# DAC_Shield_Rev_B.net
KiCad netlist of a schematic drawn in EAGLE
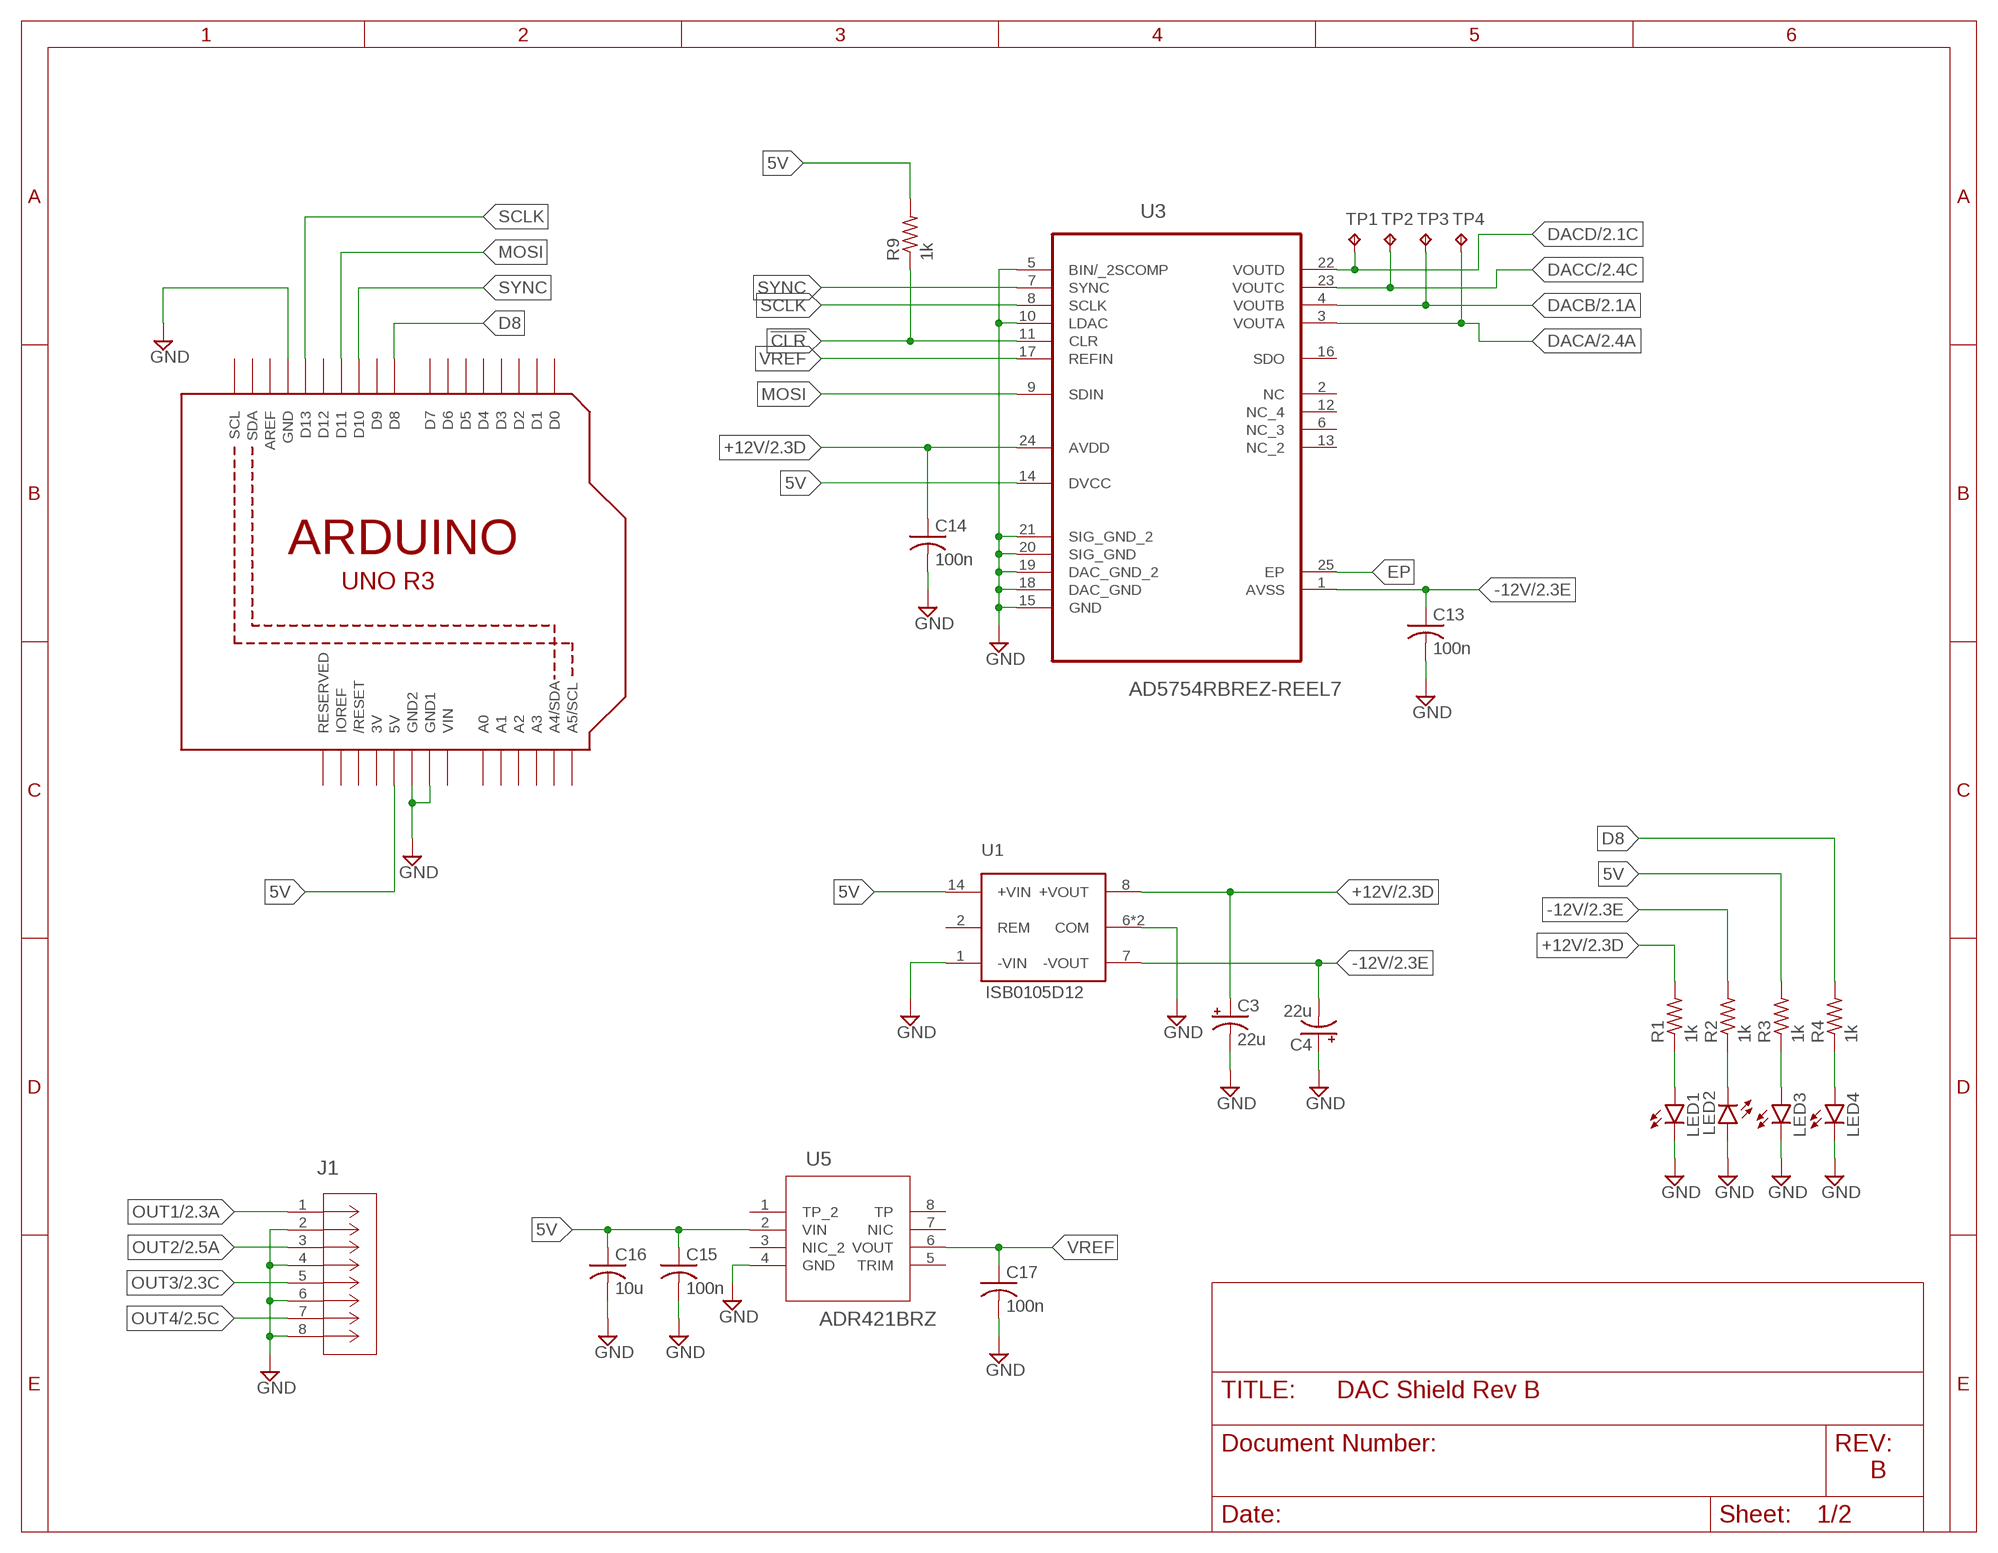
[diagram p0: schematic, sheet 1]
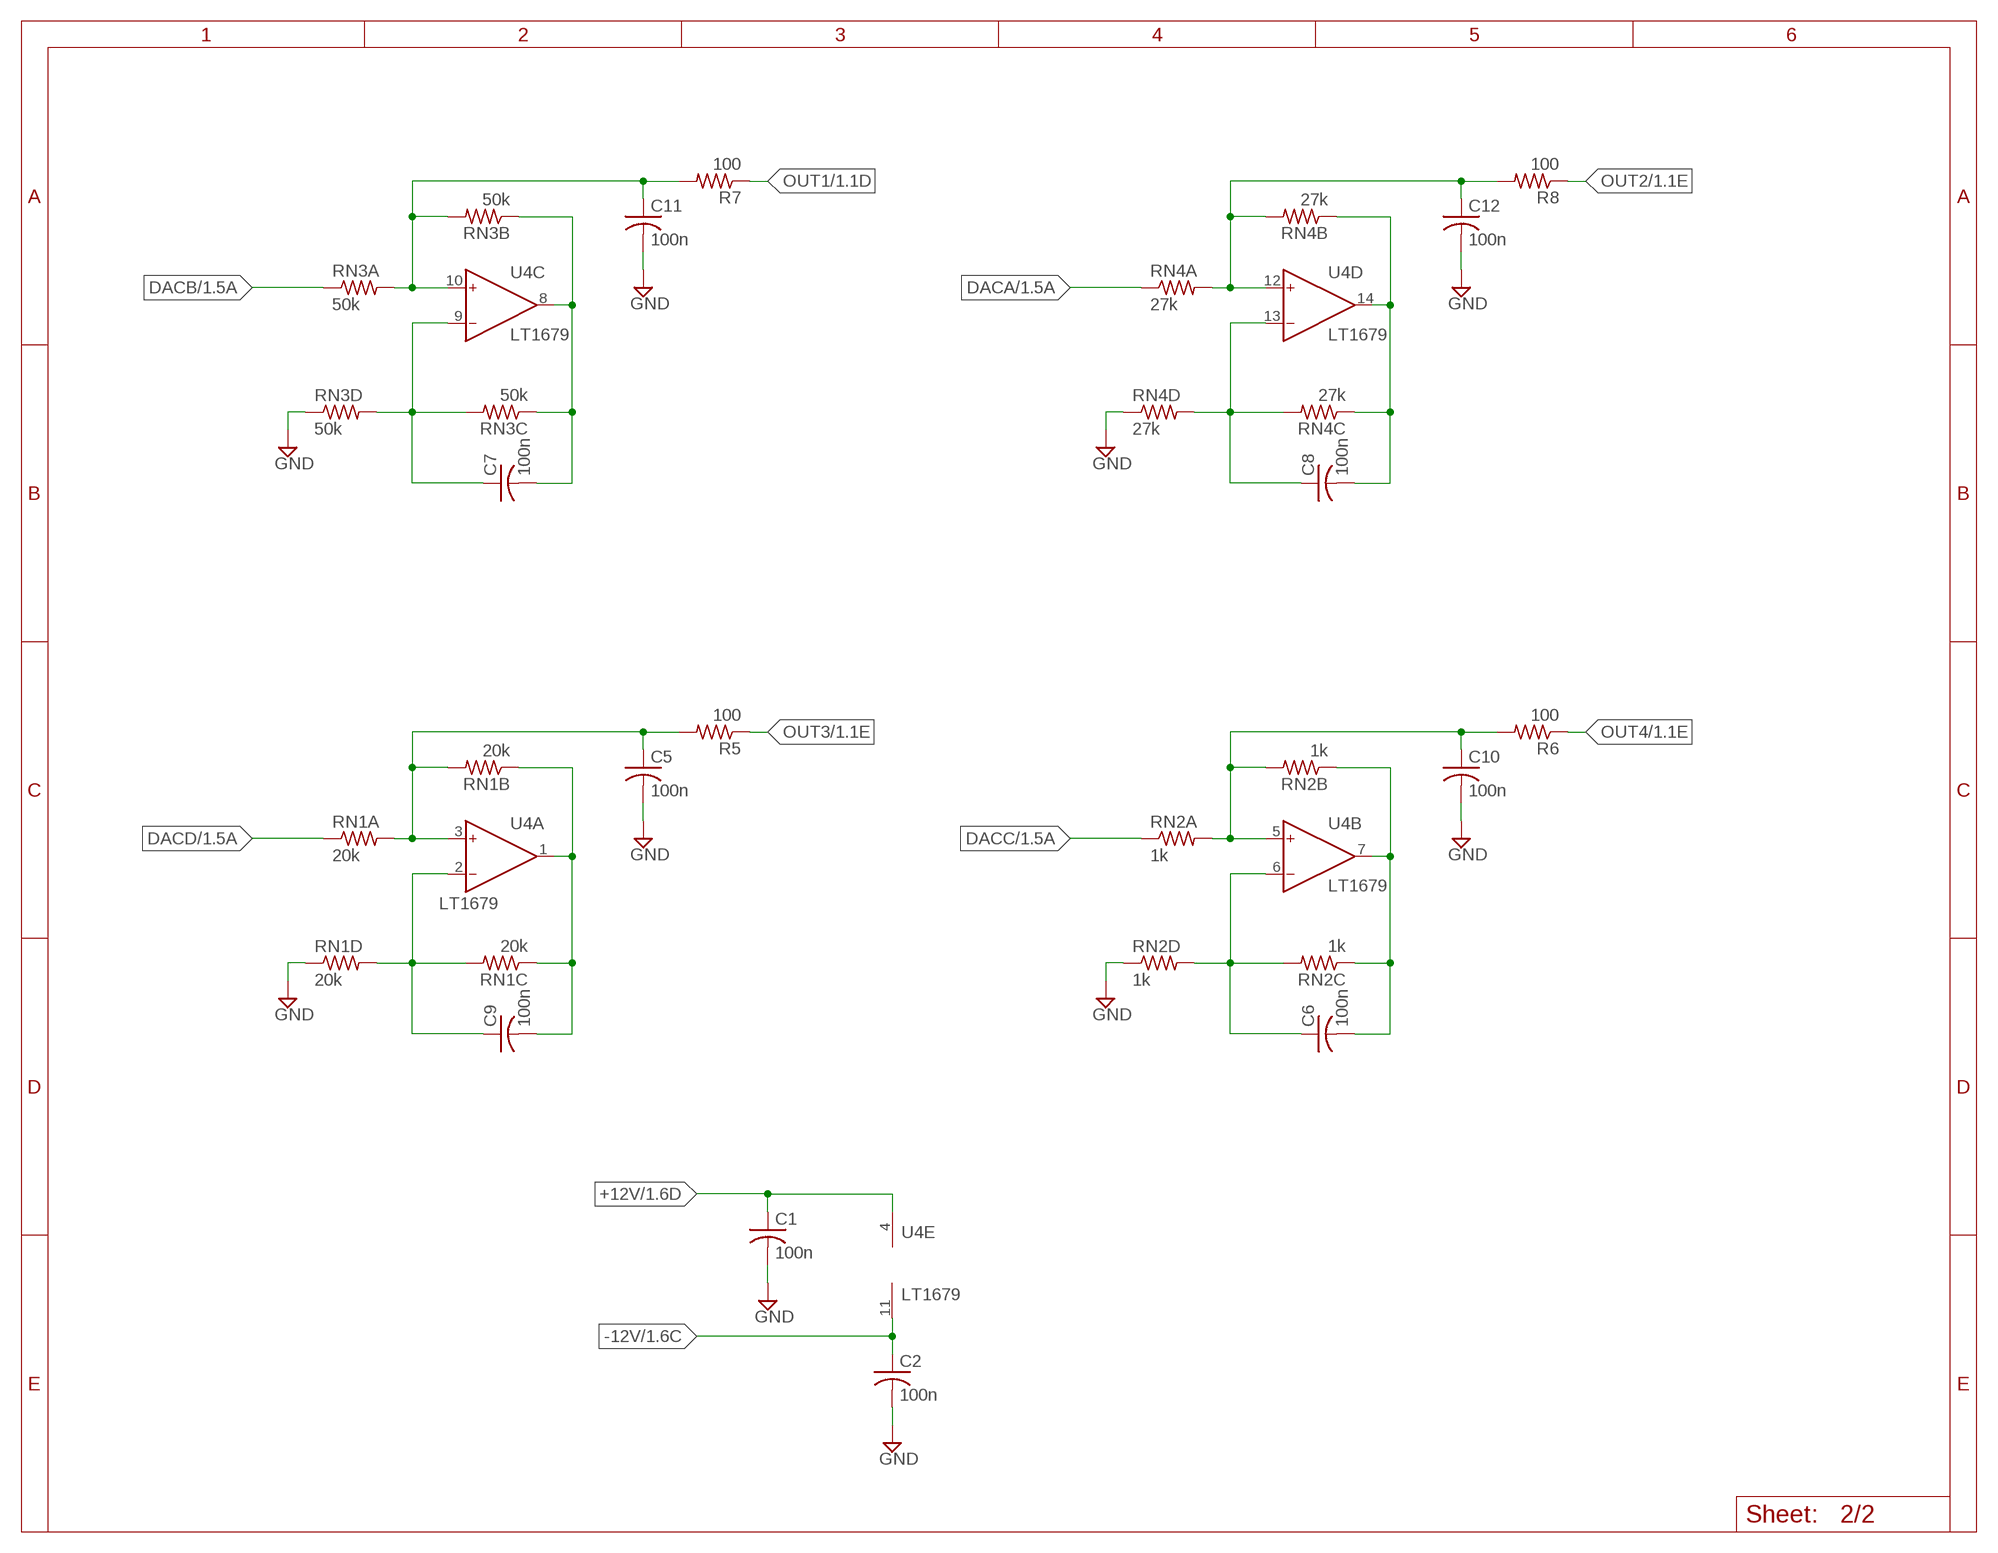
[diagram p1: schematic, sheet 2]

(export (version "E")
  (design (tool "Eeschema 10.0.6"))
  (components
    (comp (ref "C1")
      (value "100n")
      (footprint "eagle-import:C0805")
      (libsource (lib "eagle-import") (part "C-USC0805"))
    )
    (comp (ref "C2")
      (value "100n")
      (footprint "eagle-import:C0805")
      (libsource (lib "eagle-import") (part "C-USC0805"))
    )
    (comp (ref "C5")
      (value "100n")
      (footprint "eagle-import:C0805")
      (libsource (lib "eagle-import") (part "C-USC0805"))
    )
    (comp (ref "C6")
      (value "100n")
      (footprint "eagle-import:C0805")
      (libsource (lib "eagle-import") (part "C-USC0805"))
    )
    (comp (ref "C7")
      (value "100n")
      (footprint "eagle-import:C0805")
      (libsource (lib "eagle-import") (part "C-USC0805"))
    )
    (comp (ref "C8")
      (value "100n")
      (footprint "eagle-import:C0805")
      (libsource (lib "eagle-import") (part "C-USC0805"))
    )
    (comp (ref "C9")
      (value "100n")
      (footprint "eagle-import:C0805")
      (libsource (lib "eagle-import") (part "C-USC0805"))
    )
    (comp (ref "C10")
      (value "100n")
      (footprint "eagle-import:C0805")
      (libsource (lib "eagle-import") (part "C-USC0805"))
    )
    (comp (ref "C11")
      (value "100n")
      (footprint "eagle-import:C0805")
      (libsource (lib "eagle-import") (part "C-USC0805"))
    )
    (comp (ref "C12")
      (value "100n")
      (footprint "eagle-import:C0805")
      (libsource (lib "eagle-import") (part "C-USC0805"))
    )
    (comp (ref "R5")
      (value "100")
      (footprint "eagle-import:R0805")
      (libsource (lib "eagle-import") (part "R-US_R0805"))
    )
    (comp (ref "R6")
      (value "100")
      (footprint "eagle-import:R0805")
      (libsource (lib "eagle-import") (part "R-US_R0805"))
    )
    (comp (ref "R7")
      (value "100")
      (footprint "eagle-import:R0805")
      (libsource (lib "eagle-import") (part "R-US_R0805"))
    )
    (comp (ref "R8")
      (value "100")
      (footprint "eagle-import:R0805")
      (libsource (lib "eagle-import") (part "R-US_R0805"))
    )
    (comp (ref "RN1")
      (value "20k")
      (footprint "eagle-import:RESCAV80P320X150X55-8N")
      (libsource (lib "eagle-import") (part "ACASA5001U5001P1ATACASA5001U5001P1AT"))
    )
    (comp (ref "RN2")
      (value "1k")
      (footprint "eagle-import:RESCAV80P320X150X55-8N")
      (libsource (lib "eagle-import") (part "ACASA5001U5001P1ATACASA5001U5001P1AT"))
    )
    (comp (ref "RN3")
      (value "50k")
      (footprint "eagle-import:RESCAV80P320X150X55-8N")
      (libsource (lib "eagle-import") (part "ACASA5001U5001P1ATACASA5001U5001P1AT"))
    )
    (comp (ref "RN4")
      (value "27k")
      (footprint "eagle-import:RESCAV80P320X150X55-8N")
      (libsource (lib "eagle-import") (part "ACASA5001U5001P1ATACASA5001U5001P1AT"))
    )
    (comp (ref "U4")
      (value "LT1679")
      (footprint "eagle-import:R_14_ADI-M")
      (fields
        (field (name "MANUFACTURER_PART_NUMBER") "AD8648ARZ")
        (field (name "COPYRIGHT") "Copyright (C) 2023 Ultra Librarian. All rights reserved.")
      )
      (libsource (lib "eagle-import") (part "AD8648ARZR_14_ADI-M"))
    )
    (comp (ref "C3")
      (value "22u")
      (footprint "eagle-import:C_6032-28W")
      (libsource (lib "eagle-import") (part "CPOL-USC/6032-28W"))
    )
    (comp (ref "C4")
      (value "22u")
      (footprint "eagle-import:C_6032-28W")
      (libsource (lib "eagle-import") (part "CPOL-USC/6032-28W"))
    )
    (comp (ref "C13")
      (value "100n")
      (footprint "eagle-import:C0805")
      (libsource (lib "eagle-import") (part "C-USC0805"))
    )
    (comp (ref "C14")
      (value "100n")
      (footprint "eagle-import:C0805")
      (libsource (lib "eagle-import") (part "C-USC0805"))
    )
    (comp (ref "C15")
      (value "100n")
      (footprint "eagle-import:C0805")
      (libsource (lib "eagle-import") (part "C-USC0805"))
    )
    (comp (ref "C16")
      (value "10u")
      (footprint "eagle-import:C0805")
      (libsource (lib "eagle-import") (part "C-USC0805"))
    )
    (comp (ref "C17")
      (value "100n")
      (footprint "eagle-import:C0805")
      (libsource (lib "eagle-import") (part "C-USC0805"))
    )
    (comp (ref "J1")
      (value "OSTVN08A150")
      (footprint "eagle-import:CONN_OSTVN08A150_OST")
      (fields (field (name "COPYRIGHT") "Copyright (C) 2023 Ultra Librarian. All rights reserved."))
      (libsource (lib "eagle-import") (part "OSTVN08A150"))
    )
    (comp (ref "LED1")
      (value "LEDCHIPLED_0805")
      (footprint "eagle-import:CHIPLED_0805")
      (libsource (lib "eagle-import") (part "LEDCHIPLED_0805"))
    )
    (comp (ref "LED2")
      (value "LEDCHIPLED_0805")
      (footprint "eagle-import:CHIPLED_0805")
      (libsource (lib "eagle-import") (part "LEDCHIPLED_0805"))
    )
    (comp (ref "LED3")
      (value "LEDCHIPLED_0805")
      (footprint "eagle-import:CHIPLED_0805")
      (libsource (lib "eagle-import") (part "LEDCHIPLED_0805"))
    )
    (comp (ref "LED4")
      (value "LEDCHIPLED_0805")
      (footprint "eagle-import:CHIPLED_0805")
      (libsource (lib "eagle-import") (part "LEDCHIPLED_0805"))
    )
    (comp (ref "R1")
      (value "1k")
      (footprint "eagle-import:R0805")
      (libsource (lib "eagle-import") (part "R-US_R0805"))
    )
    (comp (ref "R2")
      (value "1k")
      (footprint "eagle-import:R0805")
      (libsource (lib "eagle-import") (part "R-US_R0805"))
    )
    (comp (ref "R3")
      (value "1k")
      (footprint "eagle-import:R0805")
      (libsource (lib "eagle-import") (part "R-US_R0805"))
    )
    (comp (ref "R4")
      (value "1k")
      (footprint "eagle-import:R0805")
      (libsource (lib "eagle-import") (part "R-US_R0805"))
    )
    (comp (ref "R9")
      (value "1k")
      (footprint "eagle-import:R0805")
      (libsource (lib "eagle-import") (part "R-US_R0805"))
    )
    (comp (ref "TP1")
      (value "TPB1,27")
      (footprint "eagle-import:B1,27")
      (libsource (lib "eagle-import") (part "TPB1,27"))
    )
    (comp (ref "TP2")
      (value "TPB1,27")
      (footprint "eagle-import:B1,27")
      (libsource (lib "eagle-import") (part "TPB1,27"))
    )
    (comp (ref "TP3")
      (value "TPB1,27")
      (footprint "eagle-import:B1,27")
      (libsource (lib "eagle-import") (part "TPB1,27"))
    )
    (comp (ref "TP4")
      (value "TPB1,27")
      (footprint "eagle-import:B1,27")
      (libsource (lib "eagle-import") (part "TPB1,27"))
    )
    (comp (ref "U1")
      (value "ISB0105D12")
      (footprint "eagle-import:SOP254P1860X845-14L")
      (libsource (lib "eagle-import") (part "ISB0105D12ISB0105D12"))
    )
    (comp (ref "U2")
      (value "ARDUINOR3-BPLACE")
      (footprint "eagle-import:ARDUINOR3-BPLACE")
      (libsource (lib "eagle-import") (part "ARDUINOR3-BPLACE"))
    )
    (comp (ref "U3")
      (value "AD5754RBREZ-REEL7")
      (footprint "eagle-import:SOP65P640X120-25N")
      (libsource (lib "eagle-import") (part "AD5754RBREZ-REEL7"))
    )
    (comp (ref "U5")
      (value "ADR421BRZ")
      (footprint "eagle-import:R_8_ADI")
      (fields (field (name "COPYRIGHT") "Copyright (C) 2023 Ultra Librarian. All rights reserved."))
      (libsource (lib "eagle-import") (part "ADR421BRZ"))
    )
  )
  (nets
    (net (code "1") (name "+12V") (class "Default")
      (node (ref "C1") (pin "1") (pinfunction "1_1") (pintype "passive"))
      (node (ref "C14") (pin "1") (pinfunction "1_1") (pintype "passive"))
      (node (ref "C3") (pin "+") (pinfunction "+_+") (pintype "passive"))
      (node (ref "R1") (pin "2") (pinfunction "2_2") (pintype "passive"))
      (node (ref "U1") (pin "8") (pinfunction "+VOUT_8") (pintype "bidirectional"))
      (node (ref "U3") (pin "24") (pinfunction "AVDD_24") (pintype "power_in"))
      (node (ref "U4") (pin "4") (pinfunction "V+_4") (pintype "power_in"))
    )
    (net (code "2") (name "-12V") (class "Default")
      (node (ref "C13") (pin "1") (pinfunction "1_1") (pintype "passive"))
      (node (ref "C2") (pin "1") (pinfunction "1_1") (pintype "passive"))
      (node (ref "C4") (pin "-") (pinfunction "-_-") (pintype "passive"))
      (node (ref "R2") (pin "2") (pinfunction "2_2") (pintype "passive"))
      (node (ref "U1") (pin "7") (pinfunction "-VOUT_7") (pintype "bidirectional"))
      (node (ref "U3") (pin "1") (pinfunction "AVSS_1") (pintype "passive"))
      (node (ref "U4") (pin "11") (pinfunction "V-_11") (pintype "power_in"))
    )
    (net (code "3") (name "3V") (class "Default")
      (node (ref "U2") (pin "3V") (pinfunction "3V_3V") (pintype "power_in"))
    )
    (net (code "4") (name "5V") (class "Default")
      (node (ref "C15") (pin "1") (pinfunction "1_1") (pintype "passive"))
      (node (ref "C16") (pin "1") (pinfunction "1_1") (pintype "passive"))
      (node (ref "R3") (pin "2") (pinfunction "2_2") (pintype "passive"))
      (node (ref "R9") (pin "2") (pinfunction "2_2") (pintype "passive"))
      (node (ref "U1") (pin "14") (pinfunction "+VIN_14") (pintype "bidirectional"))
      (node (ref "U2") (pin "5V") (pinfunction "5V_5V") (pintype "power_in"))
      (node (ref "U3") (pin "14") (pinfunction "DVCC_14") (pintype "power_in"))
      (node (ref "U5") (pin "2") (pinfunction "VIN_2") (pintype "passive"))
    )
    (net (code "5") (name "D8") (class "Default")
      (node (ref "R4") (pin "2") (pinfunction "2_2") (pintype "passive"))
      (node (ref "U2") (pin "D8") (pinfunction "D8_D8") (pintype "bidirectional"))
    )
    (net (code "6") (name "DACA") (class "Default")
      (node (ref "RN4") (pin "1") (pinfunction "1_1") (pintype "passive"))
      (node (ref "TP4") (pin "TP") (pinfunction "TP_TP") (pintype "input"))
      (node (ref "U3") (pin "3") (pinfunction "VOUTA_3") (pintype "passive"))
    )
    (net (code "7") (name "DACB") (class "Default")
      (node (ref "RN3") (pin "1") (pinfunction "1_1") (pintype "passive"))
      (node (ref "TP3") (pin "TP") (pinfunction "TP_TP") (pintype "input"))
      (node (ref "U3") (pin "4") (pinfunction "VOUTB_4") (pintype "passive"))
    )
    (net (code "8") (name "DACC") (class "Default")
      (node (ref "RN2") (pin "1") (pinfunction "1_1") (pintype "passive"))
      (node (ref "TP2") (pin "TP") (pinfunction "TP_TP") (pintype "input"))
      (node (ref "U3") (pin "23") (pinfunction "VOUTC_23") (pintype "passive"))
    )
    (net (code "9") (name "DACD") (class "Default")
      (node (ref "RN1") (pin "1") (pinfunction "1_1") (pintype "passive"))
      (node (ref "TP1") (pin "TP") (pinfunction "TP_TP") (pintype "input"))
      (node (ref "U3") (pin "22") (pinfunction "VOUTD_22") (pintype "passive"))
    )
    (net (code "10") (name "EP") (class "Default")
      (node (ref "U3") (pin "25") (pinfunction "EP_25") (pintype "power_in"))
    )
    (net (code "11") (name "GND") (class "Default")
      (node (ref "C1") (pin "2") (pinfunction "2_2") (pintype "passive"))
      (node (ref "C10") (pin "2") (pinfunction "2_2") (pintype "passive"))
      (node (ref "C11") (pin "2") (pinfunction "2_2") (pintype "passive"))
      (node (ref "C12") (pin "2") (pinfunction "2_2") (pintype "passive"))
      (node (ref "C13") (pin "2") (pinfunction "2_2") (pintype "passive"))
      (node (ref "C14") (pin "2") (pinfunction "2_2") (pintype "passive"))
      (node (ref "C15") (pin "2") (pinfunction "2_2") (pintype "passive"))
      (node (ref "C16") (pin "2") (pinfunction "2_2") (pintype "passive"))
      (node (ref "C17") (pin "2") (pinfunction "2_2") (pintype "passive"))
      (node (ref "C2") (pin "2") (pinfunction "2_2") (pintype "passive"))
      (node (ref "C3") (pin "-") (pinfunction "-_-") (pintype "passive"))
      (node (ref "C4") (pin "+") (pinfunction "+_+") (pintype "passive"))
      (node (ref "C5") (pin "2") (pinfunction "2_2") (pintype "passive"))
      (node (ref "J1") (pin "2") (pinfunction "2_2") (pintype "passive"))
      (node (ref "J1") (pin "4") (pinfunction "4_4") (pintype "passive"))
      (node (ref "J1") (pin "6") (pinfunction "6_6") (pintype "passive"))
      (node (ref "J1") (pin "8") (pinfunction "8_8") (pintype "passive"))
      (node (ref "LED1") (pin "C") (pinfunction "C_C") (pintype "passive"))
      (node (ref "LED2") (pin "A") (pinfunction "A_A") (pintype "passive"))
      (node (ref "LED3") (pin "C") (pinfunction "C_C") (pintype "passive"))
      (node (ref "LED4") (pin "C") (pinfunction "C_C") (pintype "passive"))
      (node (ref "RN1") (pin "4") (pinfunction "1_4") (pintype "passive"))
      (node (ref "RN2") (pin "4") (pinfunction "1_4") (pintype "passive"))
      (node (ref "RN3") (pin "4") (pinfunction "1_4") (pintype "passive"))
      (node (ref "RN4") (pin "4") (pinfunction "1_4") (pintype "passive"))
      (node (ref "U1") (pin "1") (pinfunction "-VIN_1") (pintype "bidirectional"))
      (node (ref "U1") (pin "6") (pinfunction "COM_6") (pintype "bidirectional"))
      (node (ref "U1") (pin "9") (pinfunction "COM_9") (pintype "bidirectional"))
      (node (ref "U2") (pin "GND") (pinfunction "GND_GND") (pintype "power_in"))
      (node (ref "U2") (pin "GND1") (pinfunction "GND1_GND1") (pintype "power_in"))
      (node (ref "U2") (pin "GND2") (pinfunction "GND2_GND2") (pintype "power_in"))
      (node (ref "U3") (pin "10") (pinfunction "LDAC_10") (pintype "passive"))
      (node (ref "U3") (pin "15") (pinfunction "GND_15") (pintype "passive"))
      (node (ref "U3") (pin "18") (pinfunction "DAC_GND_18") (pintype "passive"))
      (node (ref "U3") (pin "19") (pinfunction "DAC_GND_2_19") (pintype "passive"))
      (node (ref "U3") (pin "20") (pinfunction "SIG_GND_20") (pintype "passive"))
      (node (ref "U3") (pin "21") (pinfunction "SIG_GND_2_21") (pintype "passive"))
      (node (ref "U3") (pin "5") (pinfunction "BIN/_2SCOMP_5") (pintype "passive"))
      (node (ref "U5") (pin "4") (pinfunction "GND_4") (pintype "passive"))
    )
    (net (code "12") (name "MOSI") (class "Default")
      (node (ref "U2") (pin "D11") (pinfunction "D11_D11") (pintype "bidirectional"))
      (node (ref "U3") (pin "9") (pinfunction "SDIN_9") (pintype "passive"))
    )
    (net (code "13") (name "Net-(LED1-PadA)") (class "Default")
      (node (ref "LED1") (pin "A") (pinfunction "A_A") (pintype "passive"))
      (node (ref "R1") (pin "1") (pinfunction "1_1") (pintype "passive"))
    )
    (net (code "14") (name "Net-(LED2-PadC)") (class "Default")
      (node (ref "LED2") (pin "C") (pinfunction "C_C") (pintype "passive"))
      (node (ref "R2") (pin "1") (pinfunction "1_1") (pintype "passive"))
    )
    (net (code "15") (name "Net-(LED3-PadA)") (class "Default")
      (node (ref "LED3") (pin "A") (pinfunction "A_A") (pintype "passive"))
      (node (ref "R3") (pin "1") (pinfunction "1_1") (pintype "passive"))
    )
    (net (code "16") (name "Net-(LED4-PadA)") (class "Default")
      (node (ref "LED4") (pin "A") (pinfunction "A_A") (pintype "passive"))
      (node (ref "R4") (pin "1") (pinfunction "1_1") (pintype "passive"))
    )
    (net (code "17") (name "Net-(RN1A-2)") (class "Default")
      (node (ref "C5") (pin "1") (pinfunction "1_1") (pintype "passive"))
      (node (ref "R5") (pin "2") (pinfunction "2_2") (pintype "passive"))
      (node (ref "RN1") (pin "7") (pinfunction "2_7") (pintype "passive"))
      (node (ref "RN1") (pin "8") (pinfunction "2_8") (pintype "passive"))
      (node (ref "U4") (pin "3") (pinfunction "IN+_3") (pintype "input"))
    )
    (net (code "18") (name "Net-(RN1B-1)") (class "Default")
      (node (ref "C9") (pin "2") (pinfunction "2_2") (pintype "passive"))
      (node (ref "RN1") (pin "2") (pinfunction "1_2") (pintype "passive"))
      (node (ref "RN1") (pin "3") (pinfunction "1_3") (pintype "passive"))
      (node (ref "U4") (pin "1") (pinfunction "OUT_1") (pintype "output"))
    )
    (net (code "19") (name "Net-(RN1C-2)") (class "Default")
      (node (ref "C9") (pin "1") (pinfunction "1_1") (pintype "passive"))
      (node (ref "RN1") (pin "5") (pinfunction "2_5") (pintype "passive"))
      (node (ref "RN1") (pin "6") (pinfunction "2_6") (pintype "passive"))
      (node (ref "U4") (pin "2") (pinfunction "IN-_2") (pintype "input"))
    )
    (net (code "20") (name "Net-(RN2A-2)") (class "Default")
      (node (ref "C10") (pin "1") (pinfunction "1_1") (pintype "passive"))
      (node (ref "R6") (pin "2") (pinfunction "2_2") (pintype "passive"))
      (node (ref "RN2") (pin "7") (pinfunction "2_7") (pintype "passive"))
      (node (ref "RN2") (pin "8") (pinfunction "2_8") (pintype "passive"))
      (node (ref "U4") (pin "5") (pinfunction "IN+_5") (pintype "input"))
    )
    (net (code "21") (name "Net-(RN2B-1)") (class "Default")
      (node (ref "C6") (pin "2") (pinfunction "2_2") (pintype "passive"))
      (node (ref "RN2") (pin "2") (pinfunction "1_2") (pintype "passive"))
      (node (ref "RN2") (pin "3") (pinfunction "1_3") (pintype "passive"))
      (node (ref "U4") (pin "7") (pinfunction "OUT_7") (pintype "output"))
    )
    (net (code "22") (name "Net-(RN2C-2)") (class "Default")
      (node (ref "C6") (pin "1") (pinfunction "1_1") (pintype "passive"))
      (node (ref "RN2") (pin "5") (pinfunction "2_5") (pintype "passive"))
      (node (ref "RN2") (pin "6") (pinfunction "2_6") (pintype "passive"))
      (node (ref "U4") (pin "6") (pinfunction "IN-_6") (pintype "input"))
    )
    (net (code "23") (name "Net-(RN3A-2)") (class "Default")
      (node (ref "C11") (pin "1") (pinfunction "1_1") (pintype "passive"))
      (node (ref "R7") (pin "2") (pinfunction "2_2") (pintype "passive"))
      (node (ref "RN3") (pin "7") (pinfunction "2_7") (pintype "passive"))
      (node (ref "RN3") (pin "8") (pinfunction "2_8") (pintype "passive"))
      (node (ref "U4") (pin "10") (pinfunction "IN+_10") (pintype "input"))
    )
    (net (code "24") (name "Net-(RN3B-1)") (class "Default")
      (node (ref "C7") (pin "2") (pinfunction "2_2") (pintype "passive"))
      (node (ref "RN3") (pin "2") (pinfunction "1_2") (pintype "passive"))
      (node (ref "RN3") (pin "3") (pinfunction "1_3") (pintype "passive"))
      (node (ref "U4") (pin "8") (pinfunction "OUT_8") (pintype "output"))
    )
    (net (code "25") (name "Net-(RN3C-2)") (class "Default")
      (node (ref "C7") (pin "1") (pinfunction "1_1") (pintype "passive"))
      (node (ref "RN3") (pin "5") (pinfunction "2_5") (pintype "passive"))
      (node (ref "RN3") (pin "6") (pinfunction "2_6") (pintype "passive"))
      (node (ref "U4") (pin "9") (pinfunction "IN-_9") (pintype "input"))
    )
    (net (code "26") (name "Net-(RN4A-2)") (class "Default")
      (node (ref "C12") (pin "1") (pinfunction "1_1") (pintype "passive"))
      (node (ref "R8") (pin "2") (pinfunction "2_2") (pintype "passive"))
      (node (ref "RN4") (pin "7") (pinfunction "2_7") (pintype "passive"))
      (node (ref "RN4") (pin "8") (pinfunction "2_8") (pintype "passive"))
      (node (ref "U4") (pin "12") (pinfunction "IN+_12") (pintype "input"))
    )
    (net (code "27") (name "Net-(RN4B-1)") (class "Default")
      (node (ref "C8") (pin "2") (pinfunction "2_2") (pintype "passive"))
      (node (ref "RN4") (pin "2") (pinfunction "1_2") (pintype "passive"))
      (node (ref "RN4") (pin "3") (pinfunction "1_3") (pintype "passive"))
      (node (ref "U4") (pin "14") (pinfunction "OUT_14") (pintype "output"))
    )
    (net (code "28") (name "Net-(RN4C-2)") (class "Default")
      (node (ref "C8") (pin "1") (pinfunction "1_1") (pintype "passive"))
      (node (ref "RN4") (pin "5") (pinfunction "2_5") (pintype "passive"))
      (node (ref "RN4") (pin "6") (pinfunction "2_6") (pintype "passive"))
      (node (ref "U4") (pin "13") (pinfunction "IN-_13") (pintype "input"))
    )
    (net (code "29") (name "OUT1") (class "Default")
      (node (ref "J1") (pin "1") (pinfunction "1_1") (pintype "passive"))
      (node (ref "R7") (pin "1") (pinfunction "1_1") (pintype "passive"))
    )
    (net (code "30") (name "OUT2") (class "Default")
      (node (ref "J1") (pin "3") (pinfunction "3_3") (pintype "passive"))
      (node (ref "R8") (pin "1") (pinfunction "1_1") (pintype "passive"))
    )
    (net (code "31") (name "OUT3") (class "Default")
      (node (ref "J1") (pin "5") (pinfunction "5_5") (pintype "passive"))
      (node (ref "R5") (pin "1") (pinfunction "1_1") (pintype "passive"))
    )
    (net (code "32") (name "OUT4") (class "Default")
      (node (ref "J1") (pin "7") (pinfunction "7_7") (pintype "passive"))
      (node (ref "R6") (pin "1") (pinfunction "1_1") (pintype "passive"))
    )
    (net (code "33") (name "SCLK") (class "Default")
      (node (ref "U2") (pin "D13") (pinfunction "D13_D13") (pintype "bidirectional"))
      (node (ref "U3") (pin "8") (pinfunction "SCLK_8") (pintype "passive"))
    )
    (net (code "34") (name "SYNC") (class "Default")
      (node (ref "U2") (pin "D10") (pinfunction "D10_D10") (pintype "bidirectional"))
      (node (ref "U3") (pin "7") (pinfunction "SYNC_7") (pintype "passive"))
    )
    (net (code "35") (name "VIN") (class "Default")
      (node (ref "U2") (pin "VIN") (pinfunction "VIN_VIN") (pintype "power_in"))
    )
    (net (code "36") (name "VREF") (class "Default")
      (node (ref "C17") (pin "1") (pinfunction "1_1") (pintype "passive"))
      (node (ref "U3") (pin "17") (pinfunction "REFIN_17") (pintype "passive"))
      (node (ref "U5") (pin "6") (pinfunction "VOUT_6") (pintype "passive"))
    )
    (net (code "37") (name "unconnected-(U1-REM-Pad2)") (class "Default")
      (node (ref "U1") (pin "2") (pinfunction "REM_2") (pintype "bidirectional"))
    )
    (net (code "38") (name "unconnected-(U2-A4{slash}SDA-PadA4)") (class "Default")
      (node (ref "U2") (pin "A4") (pinfunction "A4/SDA_A4") (pintype "bidirectional"))
    )
    (net (code "39") (name "unconnected-(U2-A5{slash}SCL-PadA5)") (class "Default")
      (node (ref "U2") (pin "A5") (pinfunction "A5/SCL_A5") (pintype "bidirectional"))
    )
    (net (code "40") (name "unconnected-(U2-PadA0)") (class "Default")
      (node (ref "U2") (pin "A0") (pinfunction "A0_A0") (pintype "bidirectional"))
    )
    (net (code "41") (name "unconnected-(U2-PadA1)") (class "Default")
      (node (ref "U2") (pin "A1") (pinfunction "A1_A1") (pintype "bidirectional"))
    )
    (net (code "42") (name "unconnected-(U2-PadA2)") (class "Default")
      (node (ref "U2") (pin "A2") (pinfunction "A2_A2") (pintype "bidirectional"))
    )
    (net (code "43") (name "unconnected-(U2-PadA3)") (class "Default")
      (node (ref "U2") (pin "A3") (pinfunction "A3_A3") (pintype "bidirectional"))
    )
    (net (code "44") (name "unconnected-(U2-PadAREF)") (class "Default")
      (node (ref "U2") (pin "AREF") (pinfunction "AREF_AREF") (pintype "bidirectional"))
    )
    (net (code "45") (name "unconnected-(U2-PadD0)") (class "Default")
      (node (ref "U2") (pin "D0") (pinfunction "D0_D0") (pintype "bidirectional"))
    )
    (net (code "46") (name "unconnected-(U2-PadD1)") (class "Default")
      (node (ref "U2") (pin "D1") (pinfunction "D1_D1") (pintype "bidirectional"))
    )
    (net (code "47") (name "unconnected-(U2-PadD2)") (class "Default")
      (node (ref "U2") (pin "D2") (pinfunction "D2_D2") (pintype "bidirectional"))
    )
    (net (code "48") (name "unconnected-(U2-PadD3)") (class "Default")
      (node (ref "U2") (pin "D3") (pinfunction "D3_D3") (pintype "bidirectional"))
    )
    (net (code "49") (name "unconnected-(U2-PadD4)") (class "Default")
      (node (ref "U2") (pin "D4") (pinfunction "D4_D4") (pintype "bidirectional"))
    )
    (net (code "50") (name "unconnected-(U2-PadD5)") (class "Default")
      (node (ref "U2") (pin "D5") (pinfunction "D5_D5") (pintype "bidirectional"))
    )
    (net (code "51") (name "unconnected-(U2-PadD6)") (class "Default")
      (node (ref "U2") (pin "D6") (pinfunction "D6_D6") (pintype "bidirectional"))
    )
    (net (code "52") (name "unconnected-(U2-PadD7)") (class "Default")
      (node (ref "U2") (pin "D7") (pinfunction "D7_D7") (pintype "bidirectional"))
    )
    (net (code "53") (name "unconnected-(U2-PadD9)") (class "Default")
      (node (ref "U2") (pin "D9") (pinfunction "D9_D9") (pintype "bidirectional"))
    )
    (net (code "54") (name "unconnected-(U2-PadD12)") (class "Default")
      (node (ref "U2") (pin "D12") (pinfunction "D12_D12") (pintype "bidirectional"))
    )
    (net (code "55") (name "unconnected-(U2-PadIOREF)") (class "Default")
      (node (ref "U2") (pin "IOREF") (pinfunction "IOREF_IOREF") (pintype "output"))
    )
    (net (code "56") (name "unconnected-(U2-PadRESERVED)") (class "Default")
      (node (ref "U2") (pin "RESERVED") (pinfunction "RESERVED_RESERVED") (pintype "no_connect"))
    )
    (net (code "57") (name "unconnected-(U2-PadSCL)") (class "Default")
      (node (ref "U2") (pin "SCL") (pinfunction "SCL_SCL") (pintype "bidirectional"))
    )
    (net (code "58") (name "unconnected-(U2-PadSDA)") (class "Default")
      (node (ref "U2") (pin "SDA") (pinfunction "SDA_SDA") (pintype "bidirectional"))
    )
    (net (code "59") (name "unconnected-(U2-{slash}RESET-PadRESET)") (class "Default")
      (node (ref "U2") (pin "RESET") (pinfunction "/RESET_RESET") (pintype "bidirectional"))
    )
    (net (code "60") (name "unconnected-(U3-NC-Pad2)") (class "Default")
      (node (ref "U3") (pin "2") (pinfunction "NC_2") (pintype "passive"))
    )
    (net (code "61") (name "unconnected-(U3-NC_2-Pad13)") (class "Default")
      (node (ref "U3") (pin "13") (pinfunction "NC_2_13") (pintype "passive"))
    )
    (net (code "62") (name "unconnected-(U3-NC_3-Pad6)") (class "Default")
      (node (ref "U3") (pin "6") (pinfunction "NC_3_6") (pintype "passive"))
    )
    (net (code "63") (name "unconnected-(U3-NC_4-Pad12)") (class "Default")
      (node (ref "U3") (pin "12") (pinfunction "NC_4_12") (pintype "passive"))
    )
    (net (code "64") (name "unconnected-(U3-SDO-Pad16)") (class "Default")
      (node (ref "U3") (pin "16") (pinfunction "SDO_16") (pintype "passive"))
    )
    (net (code "65") (name "unconnected-(U5-NIC-Pad7)") (class "Default")
      (node (ref "U5") (pin "7") (pinfunction "NIC_7") (pintype "passive"))
    )
    (net (code "66") (name "unconnected-(U5-NIC_2-Pad3)") (class "Default")
      (node (ref "U5") (pin "3") (pinfunction "NIC_2_3") (pintype "passive"))
    )
    (net (code "67") (name "unconnected-(U5-TP-Pad8)") (class "Default")
      (node (ref "U5") (pin "8") (pinfunction "TP_8") (pintype "passive"))
    )
    (net (code "68") (name "unconnected-(U5-TP_2-Pad1)") (class "Default")
      (node (ref "U5") (pin "1") (pinfunction "TP_2_1") (pintype "passive"))
    )
    (net (code "69") (name "unconnected-(U5-TRIM-Pad5)") (class "Default")
      (node (ref "U5") (pin "5") (pinfunction "TRIM_5") (pintype "passive"))
    )
    (net (code "70") (name "~{CLR}") (class "Default")
      (node (ref "R9") (pin "1") (pinfunction "1_1") (pintype "passive"))
      (node (ref "U3") (pin "11") (pinfunction "CLR_11") (pintype "passive"))
    )
  )
)
